# INTERFACE.net
KiCad netlist of a schematic drawn in Altium Designer
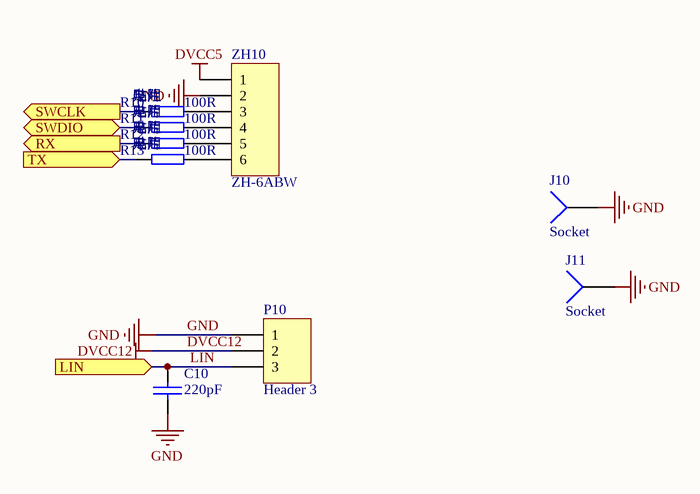
[diagram p0: INTERFACE.SchDoc]

(export (version "E")
  (design (tool "Eeschema 10.0.6"))
  (components
    (comp (ref "C10") (value "220pF") (footprint "C0402") (libsource (lib "CxyDXP_SCH") (part "CC")))
    (comp (ref "J10")
      (value "Socket")
      (footprint "SPRING_2SIDES")
      (fields (field (name "PUBLISHER") "Altium Limited"))
      (libsource (lib "Miscellaneous Connectors") (part "Socket"))
    )
    (comp (ref "J11")
      (value "Socket")
      (footprint "SPRING_2SIDES")
      (fields (field (name "PUBLISHER") "Altium Limited"))
      (libsource (lib "Miscellaneous Connectors") (part "Socket"))
    )
    (comp (ref "P10")
      (value "Header 3")
      (footprint "53426-3")
      (description "Header, 3-Pin")
      (fields (field (name "PUBLISHER") "Altium Limited"))
      (libsource (lib "Miscellaneous Connectors") (part "Header 3"))
    )
    (comp (ref "R10") (value "100R") (footprint "R0402") (libsource (lib "CxyDXP_SCH") (part "RES1")))
    (comp (ref "R11") (value "100R") (footprint "R0402") (libsource (lib "CxyDXP_SCH") (part "RES1")))
    (comp (ref "R12") (value "100R") (footprint "R0402") (libsource (lib "CxyDXP_SCH") (part "RES1")))
    (comp (ref "R13") (value "100R") (footprint "R0402") (libsource (lib "CxyDXP_SCH") (part "RES1")))
    (comp (ref "ZH10")
      (value "ZH-6ABW")
      (footprint "ZH-6ABW")
      (description "1.5mm")
      (fields (field (name "PUBLISHER") "Altium Limited"))
      (libsource (lib "Connectors") (part "ZH-6ABW"))
    )
  )
  (nets
    (net (code "1") (name "/LIN") (class "Default")
      (node (ref "C10") (pin "1") (pintype "passive"))
      (node (ref "P10") (pin "3") (pinfunction "3_3") (pintype "passive"))
    )
    (net (code "2") (name "/RX") (class "Default")
      (node (ref "R12") (pin "1") (pinfunction "1_1") (pintype "passive"))
    )
    (net (code "3") (name "/SWCLK") (class "Default")
      (node (ref "R10") (pin "1") (pinfunction "1_1") (pintype "passive"))
    )
    (net (code "4") (name "/SWDIO") (class "Default")
      (node (ref "R11") (pin "1") (pinfunction "1_1") (pintype "passive"))
    )
    (net (code "5") (name "/TX") (class "Default")
      (node (ref "R13") (pin "1") (pinfunction "1_1") (pintype "passive"))
    )
    (net (code "6") (name "DVCC5") (class "Default")
      (node (ref "ZH10") (pin "1") (pinfunction "1_1") (pintype "passive"))
    )
    (net (code "7") (name "DVCC12") (class "Default")
      (node (ref "P10") (pin "2") (pinfunction "2_2") (pintype "passive"))
    )
    (net (code "8") (name "GND") (class "Default")
      (node (ref "C10") (pin "2") (pintype "passive"))
      (node (ref "J10") (pin "1") (pinfunction "1_1") (pintype "passive"))
      (node (ref "J11") (pin "1") (pinfunction "1_1") (pintype "passive"))
      (node (ref "P10") (pin "1") (pinfunction "1_1") (pintype "passive"))
      (node (ref "ZH10") (pin "2") (pinfunction "2_2") (pintype "passive"))
    )
    (net (code "9") (name "Net-(R10-Pad2)") (class "Default")
      (node (ref "R10") (pin "2") (pinfunction "2_2") (pintype "passive"))
      (node (ref "ZH10") (pin "3") (pinfunction "3_3") (pintype "passive"))
    )
    (net (code "10") (name "Net-(R11-Pad2)") (class "Default")
      (node (ref "R11") (pin "2") (pinfunction "2_2") (pintype "passive"))
      (node (ref "ZH10") (pin "4") (pinfunction "4_4") (pintype "passive"))
    )
    (net (code "11") (name "Net-(R12-Pad2)") (class "Default")
      (node (ref "R12") (pin "2") (pinfunction "2_2") (pintype "passive"))
      (node (ref "ZH10") (pin "5") (pinfunction "5_5") (pintype "passive"))
    )
    (net (code "12") (name "Net-(R13-Pad2)") (class "Default")
      (node (ref "R13") (pin "2") (pinfunction "2_2") (pintype "passive"))
      (node (ref "ZH10") (pin "6") (pinfunction "6_6") (pintype "passive"))
    )
  )
)
